# Interface.net
KiCad netlist of a schematic drawn in Altium Designer
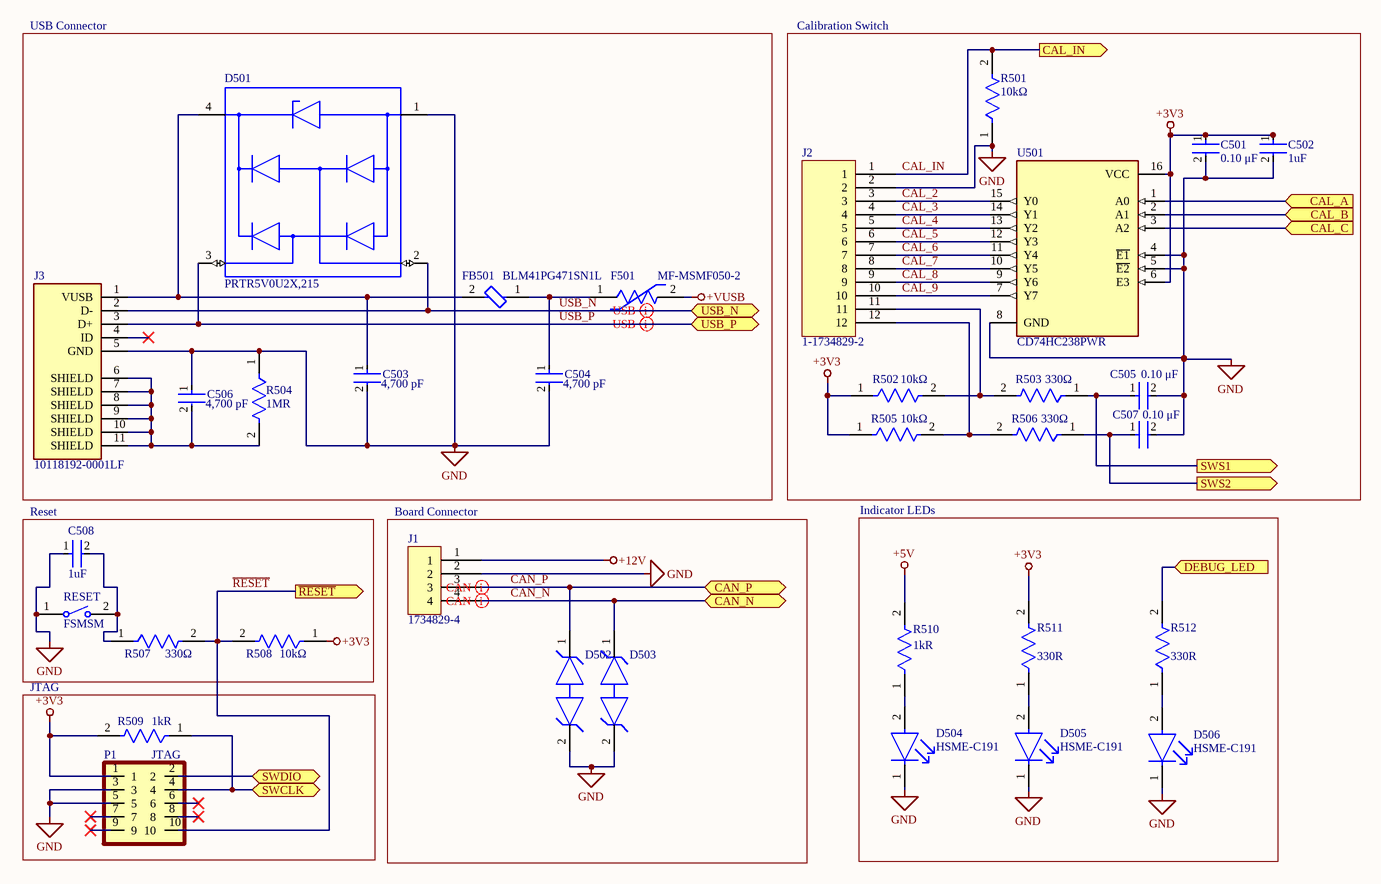
[diagram p0: Interface.SchDoc]

(export (version "E")
  (design (tool "Eeschema 10.0.6"))
  (components
    (comp (ref "C501")
      (value "C0603C104K5RACAUTO")
      (footprint "FP-C0603C-CF-MFG")
      (description "CAP CER 0.1UF 50V X7R 0603")
      (fields
        (field (name "MANUFACTURER") "KEMET")
        (field (name "OCTOPART") "https://octopart.com/c0603c104k5racauto-kemet-12563741")
        (field (name "CAPACITANCE") "0.10 μF")
      )
      (libsource (lib "Altium Content Vault") (part "b4654b650e69147ec39a6b967a45e02"))
    )
    (comp (ref "C502")
      (value "C0603C105K4RACAUTO")
      (footprint "FP-C0603C-CJ-MFG")
      (description "CAP CER 0603 1UF 16V X7R 10%")
      (fields
        (field (name "MANUFACTURER") "KEMET")
        (field (name "OCTOPART") "https://octopart.com/c0603c105k4racauto-kemet-91328491")
        (field (name "CAPACITANCE") "1uF")
      )
      (libsource (lib "Altium Content Vault") (part "b4654b650e69147ec39a6b967a45e02"))
    )
    (comp (ref "C503")
      (value "C0603C472K5RACAUTO")
      (footprint "FP-C0603C-CF-MFG")
      (description "CAP CER 4700PF 50V X7R 0603")
      (fields
        (field (name "OCTOPART") "https://octopart.com/c0603c472k5racauto-kemet-20122456")
        (field (name "TOLERANCE") "0.1")
        (field (name "CAPACITANCE") "4,700 pF")
      )
      (libsource (lib "Altium Content Vault") (part "b4654b650e69147ec39a6b967a45e02"))
    )
    (comp (ref "C504")
      (value "C0603C472K5RACAUTO")
      (footprint "FP-C0603C-CF-MFG")
      (description "CAP CER 4700PF 50V X7R 0603")
      (fields
        (field (name "OCTOPART") "https://octopart.com/c0603c472k5racauto-kemet-20122456")
        (field (name "TOLERANCE") "0.1")
        (field (name "CAPACITANCE") "4,700 pF")
      )
      (libsource (lib "Altium Content Vault") (part "b4654b650e69147ec39a6b967a45e02"))
    )
    (comp (ref "C505")
      (value "C0603C104K5RACAUTO")
      (footprint "FP-C0603C-CF-MFG")
      (description "CAP CER 0.1UF 50V X7R 0603")
      (fields
        (field (name "MANUFACTURER") "KEMET")
        (field (name "OCTOPART") "https://octopart.com/c0603c104k5racauto-kemet-12563741")
        (field (name "CAPACITANCE") "0.10 μF")
      )
      (libsource (lib "Altium Content Vault") (part "b4654b650e69147ec39a6b967a45e02"))
    )
    (comp (ref "C506")
      (value "C0603C472K5RACAUTO")
      (footprint "FP-C0603C-CF-MFG")
      (description "CAP CER 4700PF 50V X7R 0603")
      (fields
        (field (name "OCTOPART") "https://octopart.com/c0603c472k5racauto-kemet-20122456")
        (field (name "TOLERANCE") "0.1")
        (field (name "CAPACITANCE") "4,700 pF")
      )
      (libsource (lib "Altium Content Vault") (part "b4654b650e69147ec39a6b967a45e02"))
    )
    (comp (ref "C507")
      (value "C0603C104K5RACAUTO")
      (footprint "FP-C0603C-CF-MFG")
      (description "CAP CER 0.1UF 50V X7R 0603")
      (fields
        (field (name "MANUFACTURER") "KEMET")
        (field (name "OCTOPART") "https://octopart.com/c0603c104k5racauto-kemet-12563741")
        (field (name "CAPACITANCE") "0.10 μF")
      )
      (libsource (lib "Altium Content Vault") (part "b4654b650e69147ec39a6b967a45e02"))
    )
    (comp (ref "C508")
      (value "C0603C105K4RACAUTO")
      (footprint "FP-C0603C-CJ-MFG")
      (description "CAP CER 0603 1UF 16V X7R 10%")
      (fields
        (field (name "MANUFACTURER") "KEMET")
        (field (name "OCTOPART") "https://octopart.com/c0603c105k4racauto-kemet-91328491")
        (field (name "CAPACITANCE") "1uF")
      )
      (libsource (lib "Altium Content Vault") (part "b4654b650e69147ec39a6b967a45e02"))
    )
    (comp (ref "D501")
      (value "PRTR5V0U2X,215")
      (footprint "FP-SOT143B-MFG")
      (description "TVS DIODE 5.5V SOT143B")
      (libsource (lib "Altium Content Vault") (part "31e4fa1655694efd507c8a671e666ef"))
    )
    (comp (ref "D502")
      (value "SD24C-01FTG")
      (footprint "FP-SD-C-MFG")
      (description "TVS DIODE 24V 42V SOD323")
      (fields
        (field (name "OCTOPART") "https://octopart.com/sd24c-01ftg-littelfuse-46947705")
        (field (name "MANUFACTURER") "Littelfuse")
      )
      (libsource (lib "Altium Content Vault") (part "e451ab689abbe86c9c103e0410c935d"))
    )
    (comp (ref "D503")
      (value "SD24C-01FTG")
      (footprint "FP-SD-C-MFG")
      (description "TVS DIODE 24V 42V SOD323")
      (fields
        (field (name "OCTOPART") "https://octopart.com/sd24c-01ftg-littelfuse-46947705")
        (field (name "MANUFACTURER") "Littelfuse")
      )
      (libsource (lib "Altium Content Vault") (part "e451ab689abbe86c9c103e0410c935d"))
    )
    (comp (ref "D504")
      (value "HSME-C191")
      (footprint "FP-HSME-C191-MFG")
      (description "LED Uni-Color Green 570nm 2-Pin Chip LED T/R")
      (fields (field (name "MANUFACTURER") "Broadcom"))
      (libsource (lib "Altium Content Vault") (part "8706943c75ba83719d021d2fdc84c58"))
    )
    (comp (ref "D505")
      (value "HSME-C191")
      (footprint "FP-HSME-C191-MFG")
      (description "LED Uni-Color Green 570nm 2-Pin Chip LED T/R")
      (fields (field (name "MANUFACTURER") "Broadcom"))
      (libsource (lib "Altium Content Vault") (part "8706943c75ba83719d021d2fdc84c58"))
    )
    (comp (ref "D506")
      (value "HSME-C191")
      (footprint "FP-HSME-C191-MFG")
      (description "LED Uni-Color Green 570nm 2-Pin Chip LED T/R")
      (fields (field (name "MANUFACTURER") "Broadcom"))
      (libsource (lib "Altium Content Vault") (part "8706943c75ba83719d021d2fdc84c58"))
    )
    (comp (ref "F501")
      (value "MF-MSMF050-2")
      (footprint "FP-MF-MSMF050-2-MFG")
      (description "PTC RESET FUSE 15V 500MA 1812")
      (fields
        (field (name "MANUFACTURER") "Bourns")
        (field (name "OCTOPART") "https://octopart.com/mf-msmf050-2-bourns-28047")
      )
      (libsource (lib "Altium Content Vault") (part "fc31388045fc42ab786d6d00b506e9f"))
    )
    (comp (ref "FB501")
      (value "BLM41PG471SN1L")
      (footprint "FP-BLM41-0_2-a1_2-IPC_B")
      (description "Ferrite Bead, 1806, 470Ω @ 100MHz, 25%, 0.05Ω, 2A")
      (fields (field (name "TOLERANCE") "25%"))
      (libsource (lib "Altium Content Vault") (part "5f30dd21d616792df468990f7003faa"))
    )
    (comp (ref "J1")
      (value "1734829-4")
      (footprint "1734829-4")
      (description "Headers & Wire Housings 4 POS HDR R/A 1.25mm")
      (libsource (lib "Timing Display") (part "1734829-4"))
    )
    (comp (ref "J2")
      (value "1-1734829-2")
      (footprint "1-1734829-2")
      (description "Headers & Wire Housings 12 POS HDR R/A 1.25mm")
      (libsource (lib "Timing Display") (part "1-1734829-2"))
    )
    (comp (ref "J3")
      (value "10118192-0001LF")
      (footprint "101181920001LF")
      (description "Connector")
      (fields (field (name "MOUSER2 PART NUMBER") "649-10118192-0001LF"))
      (libsource (lib "UConn Formula SAE") (part "10118192-0001LF"))
    )
    (comp (ref "P1")
      (value "JTAG")
      (footprint "20021111-00010T4LF:FCI_20021111-00010T4LF")
      (description "1.27x1.27MM BTB, HEADER UNSHROUDED, VERTICAL, TH, 10 POSITIONS拢卢Double row")
      (fields
        (field (name "MP") "20021111-00010T4LF")
        (field (name "MF") "{'manufacturer': u'AMPHENOL ICC / FCI'}")
      )
      (libsource (lib "*") (part "20021111-00010T4LF"))
    )
    (comp (ref "R501")
      (value "RMCF0603JT10K0")
      (footprint "FP-RMCF0603-IPC_C")
      (description "10kΩ ±5% 0.1W 0603 Thick Film Chip Resistor AEC-Q200 compliant")
      (fields (field (name "TOLERANCE") "5%") (field (name "RESISTANCE") "10kΩ"))
      (libsource (lib "Altium Content Vault") (part "1029c3af85768c4190bb7ad29bc67b5"))
    )
    (comp (ref "R502")
      (value "RMCF0603JT10K0")
      (footprint "FP-RMCF0603-IPC_C")
      (description "10kΩ ±5% 0.1W 0603 Thick Film Chip Resistor AEC-Q200 compliant")
      (fields (field (name "TOLERANCE") "5%") (field (name "RESISTANCE") "10kΩ"))
      (libsource (lib "Altium Content Vault") (part "1029c3af85768c4190bb7ad29bc67b5"))
    )
    (comp (ref "R503")
      (value "RMCF0603JT330R")
      (footprint "FP-RMCF0603-MFG")
      (description "330Ω ±5% 0.1W 0603 Thick Film Chip Resistor AEC-Q200 compliant")
      (fields (field (name "TOLERANCE") "5%") (field (name "RESISTANCE") "330Ω"))
      (libsource (lib "Altium Content Vault") (part "1029c3af85768c4190bb7ad29bc67b5"))
    )
    (comp (ref "R504")
      (value "RMCF0603JT1M00")
      (footprint "FP-RMCF0603-IPC_B")
      (description "1MΩ ±5% 0.1W 0603 Thick Film Chip Resistor AEC-Q200 compliant")
      (fields (field (name "TOLERANCE") "5%") (field (name "RESISTANCE") "1MR"))
      (libsource (lib "Altium Content Vault") (part "1029c3af85768c4190bb7ad29bc67b5"))
    )
    (comp (ref "R505")
      (value "RMCF0603JT10K0")
      (footprint "FP-RMCF0603-IPC_C")
      (description "10kΩ ±5% 0.1W 0603 Thick Film Chip Resistor AEC-Q200 compliant")
      (fields (field (name "TOLERANCE") "5%") (field (name "RESISTANCE") "10kΩ"))
      (libsource (lib "Altium Content Vault") (part "1029c3af85768c4190bb7ad29bc67b5"))
    )
    (comp (ref "R506")
      (value "RMCF0603JT330R")
      (footprint "FP-RMCF0603-MFG")
      (description "330Ω ±5% 0.1W 0603 Thick Film Chip Resistor AEC-Q200 compliant")
      (fields (field (name "TOLERANCE") "5%") (field (name "RESISTANCE") "330Ω"))
      (libsource (lib "Altium Content Vault") (part "1029c3af85768c4190bb7ad29bc67b5"))
    )
    (comp (ref "R507")
      (value "RMCF0603JT330R")
      (footprint "FP-RMCF0603-MFG")
      (description "330Ω ±5% 0.1W 0603 Thick Film Chip Resistor AEC-Q200 compliant")
      (fields (field (name "TOLERANCE") "5%") (field (name "RESISTANCE") "330Ω"))
      (libsource (lib "Altium Content Vault") (part "1029c3af85768c4190bb7ad29bc67b5"))
    )
    (comp (ref "R508")
      (value "RMCF0603JT10K0")
      (footprint "FP-RMCF0603-IPC_C")
      (description "10kΩ ±5% 0.1W 0603 Thick Film Chip Resistor AEC-Q200 compliant")
      (fields (field (name "TOLERANCE") "5%") (field (name "RESISTANCE") "10kΩ"))
      (libsource (lib "Altium Content Vault") (part "1029c3af85768c4190bb7ad29bc67b5"))
    )
    (comp (ref "R509")
      (value "RMCF0603JT1K00")
      (footprint "FP-RMCF0603-IPC_C")
      (description "1kΩ ±5% 0.1W 0603 Thick Film Chip Resistor AEC-Q200 compliant")
      (fields (field (name "RESISTANCE") "1kR") (field (name "TOLERANCE") "5%"))
      (libsource (lib "Altium Content Vault") (part "1029c3af85768c4190bb7ad29bc67b5"))
    )
    (comp (ref "R510")
      (value "TNPW06031K00BEEA")
      (footprint "FP-TNPW0603-e3-IPC_B")
      (description "RES 1K OHM 0.1% 1/8W 0603")
      (fields (field (name "RESISTANCE") "1kR"))
      (libsource (lib "Altium Content Vault") (part "1029c3af85768c4190bb7ad29bc67b5"))
    )
    (comp (ref "R511")
      (value "RMCF0603FT330R")
      (footprint "FP-RMCF0603-MFG")
      (description "330Ω ±1% 0.1W 0603 Thick Film Chip Resistor AEC-Q200 compliant")
      (fields (field (name "RESISTANCE") "330R") (field (name "TOLERANCE") "1%"))
      (libsource (lib "Altium Content Vault") (part "1029c3af85768c4190bb7ad29bc67b5"))
    )
    (comp (ref "R512")
      (value "RMCF0603FT330R")
      (footprint "FP-RMCF0603-MFG")
      (description "330Ω ±1% 0.1W 0603 Thick Film Chip Resistor AEC-Q200 compliant")
      (fields (field (name "RESISTANCE") "330R") (field (name "TOLERANCE") "1%"))
      (libsource (lib "Altium Content Vault") (part "1029c3af85768c4190bb7ad29bc67b5"))
    )
    (comp (ref "RESET")
      (value "FSMSM")
      (footprint "TECO-FSMSM-2_V")
      (description "FSMSM Push Button Switch, 50 mA, -35 to 85 degC, 2-Pin SMD, RoHS, Bulk")
      (fields (field (name "MANUFACTURER") "TE Connectivity"))
      (libsource (lib "Altium Content Vault") (part "SW-SPST-2_C"))
    )
    (comp (ref "U501")
      (value "CD74HC238PWR")
      (footprint "FP-PW0016A-IPC_B")
      (description "IC DECODER/DEMUX 1X3:8 16TSSOP")
      (libsource (lib "Altium Content Vault") (part "f089b561ce8a4d050bfb0896b82f489"))
    )
  )
  (nets
    (net (code "1") (name "+3V3") (class "Default")
      (node (ref "C501") (pin "1") (pinfunction "1_1") (pintype "passive"))
      (node (ref "C502") (pin "1") (pinfunction "1_1") (pintype "passive"))
      (node (ref "P1") (pin "1") (pinfunction "1_1") (pintype "passive"))
      (node (ref "R502") (pin "1") (pinfunction "1_1") (pintype "passive"))
      (node (ref "R505") (pin "1") (pinfunction "1_1") (pintype "passive"))
      (node (ref "R508") (pin "1") (pinfunction "1_1") (pintype "passive"))
      (node (ref "R509") (pin "2") (pinfunction "2_2") (pintype "passive"))
      (node (ref "R511") (pin "2") (pinfunction "2_2") (pintype "passive"))
      (node (ref "U501") (pin "16") (pinfunction "VCC_16") (pintype "power_in"))
      (node (ref "U501") (pin "6") (pinfunction "E3_6") (pintype "input"))
    )
    (net (code "2") (name "+5V") (class "Default")
      (node (ref "R510") (pin "2") (pinfunction "2_2") (pintype "passive"))
    )
    (net (code "3") (name "+12V") (class "Default")
      (node (ref "J1") (pin "1") (pinfunction "1_1") (pintype "passive"))
    )
    (net (code "4") (name "+VUSB") (class "Default")
      (node (ref "F501") (pin "2") (pinfunction "2_2") (pintype "passive"))
    )
    (net (code "5") (name "/CAL_2") (class "Default")
      (node (ref "J2") (pin "3") (pinfunction "3_3") (pintype "passive"))
      (node (ref "U501") (pin "15") (pinfunction "Y0_15") (pintype "output"))
    )
    (net (code "6") (name "/CAL_3") (class "Default")
      (node (ref "J2") (pin "4") (pinfunction "4_4") (pintype "passive"))
      (node (ref "U501") (pin "14") (pinfunction "Y1_14") (pintype "output"))
    )
    (net (code "7") (name "/CAL_4") (class "Default")
      (node (ref "J2") (pin "5") (pinfunction "5_5") (pintype "passive"))
      (node (ref "U501") (pin "13") (pinfunction "Y2_13") (pintype "output"))
    )
    (net (code "8") (name "/CAL_5") (class "Default")
      (node (ref "J2") (pin "6") (pinfunction "6_6") (pintype "passive"))
      (node (ref "U501") (pin "12") (pinfunction "Y3_12") (pintype "output"))
    )
    (net (code "9") (name "/CAL_6") (class "Default")
      (node (ref "J2") (pin "7") (pinfunction "7_7") (pintype "passive"))
      (node (ref "U501") (pin "11") (pinfunction "Y4_11") (pintype "output"))
    )
    (net (code "10") (name "/CAL_7") (class "Default")
      (node (ref "J2") (pin "8") (pinfunction "8_8") (pintype "passive"))
      (node (ref "U501") (pin "10") (pinfunction "Y5_10") (pintype "output"))
    )
    (net (code "11") (name "/CAL_8") (class "Default")
      (node (ref "J2") (pin "9") (pinfunction "9_9") (pintype "passive"))
      (node (ref "U501") (pin "9") (pinfunction "Y6_9") (pintype "output"))
    )
    (net (code "12") (name "/CAL_9") (class "Default")
      (node (ref "J2") (pin "10") (pinfunction "10_10") (pintype "passive"))
      (node (ref "U501") (pin "7") (pinfunction "Y7_7") (pintype "output"))
    )
    (net (code "13") (name "/CAL_A") (class "Default")
      (node (ref "U501") (pin "1") (pinfunction "A0_1") (pintype "input"))
    )
    (net (code "14") (name "/CAL_B") (class "Default")
      (node (ref "U501") (pin "2") (pinfunction "A1_2") (pintype "input"))
    )
    (net (code "15") (name "/CAL_C") (class "Default")
      (node (ref "U501") (pin "3") (pinfunction "A2_3") (pintype "input"))
    )
    (net (code "16") (name "/CAL_IN") (class "Default")
      (node (ref "J2") (pin "1") (pinfunction "1_1") (pintype "passive"))
      (node (ref "R501") (pin "2") (pinfunction "2_2") (pintype "passive"))
    )
    (net (code "17") (name "/CAN_N") (class "Default")
      (node (ref "D503") (pin "1") (pinfunction "1_1") (pintype "passive"))
      (node (ref "J1") (pin "4") (pinfunction "4_4") (pintype "passive"))
    )
    (net (code "18") (name "/CAN_P") (class "Default")
      (node (ref "D502") (pin "1") (pinfunction "1_1") (pintype "passive"))
      (node (ref "J1") (pin "3") (pinfunction "3_3") (pintype "passive"))
    )
    (net (code "19") (name "/DEBUG_LED") (class "Default")
      (node (ref "R512") (pin "2") (pinfunction "2_2") (pintype "passive"))
    )
    (net (code "20") (name "/SWCLK") (class "Default")
      (node (ref "P1") (pin "4") (pinfunction "4_4") (pintype "passive"))
      (node (ref "R509") (pin "1") (pinfunction "1_1") (pintype "passive"))
    )
    (net (code "21") (name "/SWDIO") (class "Default")
      (node (ref "P1") (pin "2") (pinfunction "2_2") (pintype "passive"))
    )
    (net (code "22") (name "/SWS1") (class "Default")
      (node (ref "C505") (pin "1") (pinfunction "1_1") (pintype "passive"))
      (node (ref "R503") (pin "1") (pinfunction "1_1") (pintype "passive"))
    )
    (net (code "23") (name "/SWS2") (class "Default")
      (node (ref "C507") (pin "1") (pinfunction "1_1") (pintype "passive"))
      (node (ref "R506") (pin "1") (pinfunction "1_1") (pintype "passive"))
    )
    (net (code "24") (name "/USB_N") (class "Default")
      (node (ref "D501") (pin "2") (pinfunction "I/O_1_2") (pintype "bidirectional"))
      (node (ref "J3") (pin "2") (pinfunction "D-_2") (pintype "passive"))
    )
    (net (code "25") (name "/USB_P") (class "Default")
      (node (ref "D501") (pin "3") (pinfunction "I/O_2_3") (pintype "bidirectional"))
      (node (ref "J3") (pin "3") (pinfunction "D+_3") (pintype "passive"))
    )
    (net (code "26") (name "/~{RESET}") (class "Default")
      (node (ref "P1") (pin "10") (pinfunction "10_10") (pintype "passive"))
      (node (ref "R507") (pin "2") (pinfunction "2_2") (pintype "passive"))
      (node (ref "R508") (pin "2") (pinfunction "2_2") (pintype "passive"))
    )
    (net (code "27") (name "GND") (class "Default")
      (node (ref "C501") (pin "2") (pinfunction "2_2") (pintype "passive"))
      (node (ref "C502") (pin "2") (pinfunction "2_2") (pintype "passive"))
      (node (ref "C503") (pin "2") (pinfunction "2_2") (pintype "passive"))
      (node (ref "C504") (pin "2") (pinfunction "2_2") (pintype "passive"))
      (node (ref "C505") (pin "2") (pinfunction "2_2") (pintype "passive"))
      (node (ref "C506") (pin "1") (pinfunction "1_1") (pintype "passive"))
      (node (ref "C507") (pin "2") (pinfunction "2_2") (pintype "passive"))
      (node (ref "C508") (pin "1") (pinfunction "1_1") (pintype "passive"))
      (node (ref "D501") (pin "1") (pinfunction "GND_1") (pintype "power_in"))
      (node (ref "D502") (pin "2") (pinfunction "2_2") (pintype "passive"))
      (node (ref "D503") (pin "2") (pinfunction "2_2") (pintype "passive"))
      (node (ref "D504") (pin "1") (pinfunction "C_1") (pintype "passive"))
      (node (ref "D505") (pin "1") (pinfunction "C_1") (pintype "passive"))
      (node (ref "D506") (pin "1") (pinfunction "C_1") (pintype "passive"))
      (node (ref "J1") (pin "2") (pinfunction "2_2") (pintype "passive"))
      (node (ref "J2") (pin "2") (pinfunction "2_2") (pintype "passive"))
      (node (ref "J3") (pin "5") (pinfunction "GND_5") (pintype "passive"))
      (node (ref "P1") (pin "3") (pinfunction "3_3") (pintype "passive"))
      (node (ref "P1") (pin "5") (pinfunction "5_5") (pintype "passive"))
      (node (ref "R501") (pin "1") (pinfunction "1_1") (pintype "passive"))
      (node (ref "R504") (pin "1") (pinfunction "1_1") (pintype "passive"))
      (node (ref "RESET") (pin "1") (pinfunction "1_1") (pintype "passive"))
      (node (ref "U501") (pin "4") (pinfunction "~{E1}_4") (pintype "input"))
      (node (ref "U501") (pin "5") (pinfunction "~{E2}_5") (pintype "input"))
      (node (ref "U501") (pin "8") (pinfunction "GND_8") (pintype "power_in"))
    )
    (net (code "28") (name "Net-(C504-Pad1)") (class "Default")
      (node (ref "C504") (pin "1") (pinfunction "1_1") (pintype "passive"))
      (node (ref "F501") (pin "1") (pinfunction "1_1") (pintype "passive"))
      (node (ref "FB501") (pin "1") (pinfunction "1_1") (pintype "passive"))
    )
    (net (code "29") (name "Net-(C506-Pad2)") (class "Default")
      (node (ref "C506") (pin "2") (pinfunction "2_2") (pintype "passive"))
      (node (ref "J3") (pin "10") (pinfunction "SHIELD_10") (pintype "passive"))
      (node (ref "J3") (pin "11") (pinfunction "SHIELD_11") (pintype "passive"))
      (node (ref "J3") (pin "6") (pinfunction "SHIELD_6") (pintype "passive"))
      (node (ref "J3") (pin "7") (pinfunction "SHIELD_7") (pintype "passive"))
      (node (ref "J3") (pin "8") (pinfunction "SHIELD_8") (pintype "passive"))
      (node (ref "J3") (pin "9") (pinfunction "SHIELD_9") (pintype "passive"))
      (node (ref "R504") (pin "2") (pinfunction "2_2") (pintype "passive"))
    )
    (net (code "30") (name "Net-(C508-Pad2)") (class "Default")
      (node (ref "C508") (pin "2") (pinfunction "2_2") (pintype "passive"))
      (node (ref "R507") (pin "1") (pinfunction "1_1") (pintype "passive"))
      (node (ref "RESET") (pin "2") (pinfunction "2_2") (pintype "passive"))
    )
    (net (code "31") (name "Net-(D501-VCC)") (class "Default")
      (node (ref "C503") (pin "1") (pinfunction "1_1") (pintype "passive"))
      (node (ref "D501") (pin "4") (pinfunction "VCC_4") (pintype "power_in"))
      (node (ref "FB501") (pin "2") (pinfunction "2_2") (pintype "passive"))
      (node (ref "J3") (pin "1") (pinfunction "VUSB_1") (pintype "passive"))
    )
    (net (code "32") (name "Net-(D504-A)") (class "Default")
      (node (ref "D504") (pin "2") (pinfunction "A_2") (pintype "passive"))
      (node (ref "R510") (pin "1") (pinfunction "1_1") (pintype "passive"))
    )
    (net (code "33") (name "Net-(D505-A)") (class "Default")
      (node (ref "D505") (pin "2") (pinfunction "A_2") (pintype "passive"))
      (node (ref "R511") (pin "1") (pinfunction "1_1") (pintype "passive"))
    )
    (net (code "34") (name "Net-(D506-A)") (class "Default")
      (node (ref "D506") (pin "2") (pinfunction "A_2") (pintype "passive"))
      (node (ref "R512") (pin "1") (pinfunction "1_1") (pintype "passive"))
    )
    (net (code "35") (name "Net-(J2-Pad11)") (class "Default")
      (node (ref "J2") (pin "11") (pinfunction "11_11") (pintype "passive"))
      (node (ref "R502") (pin "2") (pinfunction "2_2") (pintype "passive"))
      (node (ref "R503") (pin "2") (pinfunction "2_2") (pintype "passive"))
    )
    (net (code "36") (name "Net-(J2-Pad12)") (class "Default")
      (node (ref "J2") (pin "12") (pinfunction "12_12") (pintype "passive"))
      (node (ref "R505") (pin "2") (pinfunction "2_2") (pintype "passive"))
      (node (ref "R506") (pin "2") (pinfunction "2_2") (pintype "passive"))
    )
    (net (code "37") (name "unconnected-(J3-ID-Pad4)") (class "Default")
      (node (ref "J3") (pin "4") (pinfunction "ID_4") (pintype "passive+no_connect"))
    )
    (net (code "38") (name "unconnected-(P1-Pad6)") (class "Default")
      (node (ref "P1") (pin "6") (pinfunction "6_6") (pintype "passive+no_connect"))
    )
    (net (code "39") (name "unconnected-(P1-Pad7)") (class "Default")
      (node (ref "P1") (pin "7") (pinfunction "7_7") (pintype "passive+no_connect"))
    )
    (net (code "40") (name "unconnected-(P1-Pad8)") (class "Default")
      (node (ref "P1") (pin "8") (pinfunction "8_8") (pintype "passive+no_connect"))
    )
    (net (code "41") (name "unconnected-(P1-Pad9)") (class "Default")
      (node (ref "P1") (pin "9") (pinfunction "9_9") (pintype "passive+no_connect"))
    )
  )
)
